# untitled.net
KiCad netlist of a schematic drawn in EAGLE
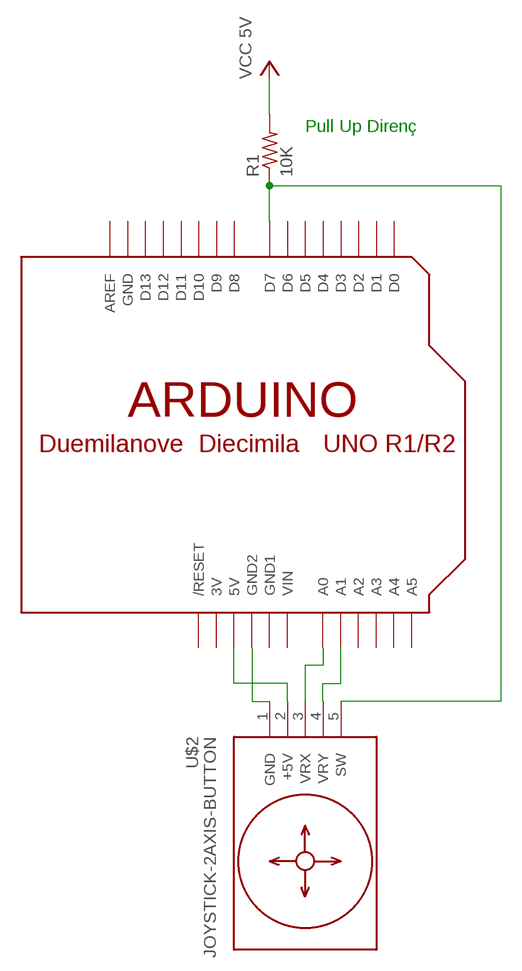
[diagram p0: schematic, sheet 1]

(export (version "E")
  (design (tool "Eeschema 10.0.6"))
  (components
    (comp (ref "R1")
      (value "10K")
      (footprint "eagle-import:0204_5")
      (libsource (lib "eagle-import") (part "R-US_0204/5"))
    )
    (comp (ref "U$1")
      (value "ARDUINOUNO")
      (footprint "eagle-import:ARDUINO")
      (libsource (lib "eagle-import") (part "ARDUINOUNO"))
    )
    (comp (ref "U$2")
      (value "JOYSTICK-2AXIS-BUTTON")
      (footprint "eagle-import:JOYSTICK-2AXIS-BUTTON")
      (libsource (lib "eagle-import") (part "JOYSTICK-2AXIS-BUTTON"))
    )
  )
  (nets
    (net (code "1") (name "/3V") (class "Default")
      (node (ref "U$1") (pin "3V") (pinfunction "3V_3V") (pintype "power_in"))
    )
    (net (code "2") (name "/GND") (class "Default")
      (node (ref "U$1") (pin "GND") (pinfunction "GND_GND") (pintype "power_in"))
    )
    (net (code "3") (name "/GND1") (class "Default")
      (node (ref "U$1") (pin "GND1") (pinfunction "GND1_GND1") (pintype "power_in"))
    )
    (net (code "4") (name "/VIN") (class "Default")
      (node (ref "U$1") (pin "VIN") (pinfunction "VIN_VIN") (pintype "power_in"))
    )
    (net (code "5") (name "Net-(U$2-+5V)") (class "Default")
      (node (ref "U$1") (pin "5V") (pinfunction "5V_5V") (pintype "power_in"))
      (node (ref "U$2") (pin "2") (pinfunction "+5V_2") (pintype "power_in"))
    )
    (net (code "6") (name "Net-(U$2-GND)") (class "Default")
      (node (ref "U$1") (pin "GND2") (pinfunction "GND2_GND2") (pintype "power_in"))
      (node (ref "U$2") (pin "1") (pinfunction "GND_1") (pintype "power_in"))
    )
    (net (code "7") (name "Net-(U$2-SW)") (class "Default")
      (node (ref "R1") (pin "1") (pinfunction "1_1") (pintype "passive"))
      (node (ref "U$1") (pin "D7") (pinfunction "D7_D7") (pintype "bidirectional"))
      (node (ref "U$2") (pin "5") (pinfunction "SW_5") (pintype "passive"))
    )
    (net (code "8") (name "Net-(U$2-VRX)") (class "Default")
      (node (ref "U$1") (pin "A0") (pinfunction "A0_A0") (pintype "bidirectional"))
      (node (ref "U$2") (pin "3") (pinfunction "VRX_3") (pintype "passive"))
    )
    (net (code "9") (name "Net-(U$2-VRY)") (class "Default")
      (node (ref "U$1") (pin "A1") (pinfunction "A1_A1") (pintype "bidirectional"))
      (node (ref "U$2") (pin "4") (pinfunction "VRY_4") (pintype "passive"))
    )
    (net (code "10") (name "VCC 5V") (class "Default")
      (node (ref "R1") (pin "2") (pinfunction "2_2") (pintype "passive"))
    )
    (net (code "11") (name "unconnected-(U$1-PadA2)") (class "Default")
      (node (ref "U$1") (pin "A2") (pinfunction "A2_A2") (pintype "bidirectional"))
    )
    (net (code "12") (name "unconnected-(U$1-PadA3)") (class "Default")
      (node (ref "U$1") (pin "A3") (pinfunction "A3_A3") (pintype "bidirectional"))
    )
    (net (code "13") (name "unconnected-(U$1-PadA4)") (class "Default")
      (node (ref "U$1") (pin "A4") (pinfunction "A4_A4") (pintype "bidirectional"))
    )
    (net (code "14") (name "unconnected-(U$1-PadA5)") (class "Default")
      (node (ref "U$1") (pin "A5") (pinfunction "A5_A5") (pintype "bidirectional"))
    )
    (net (code "15") (name "unconnected-(U$1-PadAREF)") (class "Default")
      (node (ref "U$1") (pin "AREF") (pinfunction "AREF_AREF") (pintype "bidirectional"))
    )
    (net (code "16") (name "unconnected-(U$1-PadD0)") (class "Default")
      (node (ref "U$1") (pin "D0") (pinfunction "D0_D0") (pintype "bidirectional"))
    )
    (net (code "17") (name "unconnected-(U$1-PadD1)") (class "Default")
      (node (ref "U$1") (pin "D1") (pinfunction "D1_D1") (pintype "bidirectional"))
    )
    (net (code "18") (name "unconnected-(U$1-PadD2)") (class "Default")
      (node (ref "U$1") (pin "D2") (pinfunction "D2_D2") (pintype "bidirectional"))
    )
    (net (code "19") (name "unconnected-(U$1-PadD3)") (class "Default")
      (node (ref "U$1") (pin "D3") (pinfunction "D3_D3") (pintype "bidirectional"))
    )
    (net (code "20") (name "unconnected-(U$1-PadD4)") (class "Default")
      (node (ref "U$1") (pin "D4") (pinfunction "D4_D4") (pintype "bidirectional"))
    )
    (net (code "21") (name "unconnected-(U$1-PadD5)") (class "Default")
      (node (ref "U$1") (pin "D5") (pinfunction "D5_D5") (pintype "bidirectional"))
    )
    (net (code "22") (name "unconnected-(U$1-PadD6)") (class "Default")
      (node (ref "U$1") (pin "D6") (pinfunction "D6_D6") (pintype "bidirectional"))
    )
    (net (code "23") (name "unconnected-(U$1-PadD8)") (class "Default")
      (node (ref "U$1") (pin "D8") (pinfunction "D8_D8") (pintype "bidirectional"))
    )
    (net (code "24") (name "unconnected-(U$1-PadD9)") (class "Default")
      (node (ref "U$1") (pin "D9") (pinfunction "D9_D9") (pintype "bidirectional"))
    )
    (net (code "25") (name "unconnected-(U$1-PadD10)") (class "Default")
      (node (ref "U$1") (pin "D10") (pinfunction "D10_D10") (pintype "bidirectional"))
    )
    (net (code "26") (name "unconnected-(U$1-PadD11)") (class "Default")
      (node (ref "U$1") (pin "D11") (pinfunction "D11_D11") (pintype "bidirectional"))
    )
    (net (code "27") (name "unconnected-(U$1-PadD12)") (class "Default")
      (node (ref "U$1") (pin "D12") (pinfunction "D12_D12") (pintype "bidirectional"))
    )
    (net (code "28") (name "unconnected-(U$1-PadD13)") (class "Default")
      (node (ref "U$1") (pin "D13") (pinfunction "D13_D13") (pintype "bidirectional"))
    )
    (net (code "29") (name "unconnected-(U$1-{slash}RESET-PadRESET)") (class "Default")
      (node (ref "U$1") (pin "RESET") (pinfunction "/RESET_RESET") (pintype "bidirectional"))
    )
  )
)
